# relay_edit.net
KiCad netlist of a schematic drawn in EAGLE
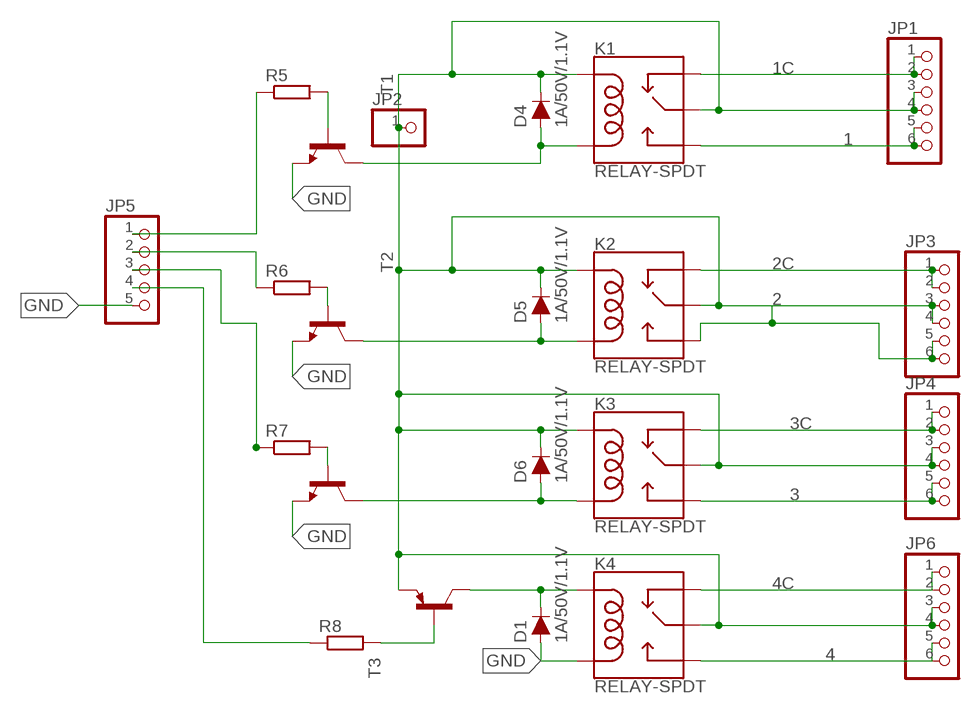
[diagram p0: schematic, sheet 1]

(export (version "E")
  (design (tool "Eeschema 10.0.6"))
  (components
    (comp (ref "D1")
      (value "1A/50V/1.1V")
      (footprint "eagle-import:DIODE-1N4001")
      (libsource (lib "eagle-import") (part "DIODE-PTH"))
    )
    (comp (ref "D4")
      (value "1A/50V/1.1V")
      (footprint "eagle-import:DIODE-1N4001")
      (libsource (lib "eagle-import") (part "DIODE-PTH"))
    )
    (comp (ref "D5")
      (value "1A/50V/1.1V")
      (footprint "eagle-import:DIODE-1N4001")
      (libsource (lib "eagle-import") (part "DIODE-PTH"))
    )
    (comp (ref "D6")
      (value "1A/50V/1.1V")
      (footprint "eagle-import:DIODE-1N4001")
      (libsource (lib "eagle-import") (part "DIODE-PTH"))
    )
    (comp (ref "JP1")
      (value "PINHD-1X6")
      (footprint "eagle-import:1X06")
      (libsource (lib "eagle-import") (part "PINHD-1X6"))
    )
    (comp (ref "JP2")
      (value "PINHD-1X1")
      (footprint "eagle-import:1X01")
      (libsource (lib "eagle-import") (part "PINHD-1X1"))
    )
    (comp (ref "JP3")
      (value "PINHD-1X6")
      (footprint "eagle-import:1X06")
      (libsource (lib "eagle-import") (part "PINHD-1X6"))
    )
    (comp (ref "JP4")
      (value "PINHD-1X6")
      (footprint "eagle-import:1X06")
      (libsource (lib "eagle-import") (part "PINHD-1X6"))
    )
    (comp (ref "JP5")
      (value "PINHD-1X5")
      (footprint "eagle-import:1X05")
      (libsource (lib "eagle-import") (part "PINHD-1X5"))
    )
    (comp (ref "JP6")
      (value "PINHD-1X6")
      (footprint "eagle-import:1X06")
      (libsource (lib "eagle-import") (part "PINHD-1X6"))
    )
    (comp (ref "K1")
      (value "RELAY-SPDT")
      (footprint "eagle-import:RELAY_G5LE")
      (libsource (lib "eagle-import") (part "RELAY-SPDT"))
    )
    (comp (ref "K2")
      (value "RELAY-SPDT")
      (footprint "eagle-import:RELAY_G5LE")
      (libsource (lib "eagle-import") (part "RELAY-SPDT"))
    )
    (comp (ref "K3")
      (value "RELAY-SPDT")
      (footprint "eagle-import:RELAY_G5LE")
      (libsource (lib "eagle-import") (part "RELAY-SPDT"))
    )
    (comp (ref "K4")
      (value "RELAY-SPDT")
      (footprint "eagle-import:RELAY_G5LE")
      (libsource (lib "eagle-import") (part "RELAY-SPDT"))
    )
    (comp (ref "R5")
      (value "R-EU_0204/5")
      (footprint "eagle-import:0204_5")
      (libsource (lib "eagle-import") (part "R-EU_0204/5"))
    )
    (comp (ref "R6")
      (value "R-EU_0204/5")
      (footprint "eagle-import:0204_5")
      (libsource (lib "eagle-import") (part "R-EU_0204/5"))
    )
    (comp (ref "R7")
      (value "R-EU_0204/5")
      (footprint "eagle-import:0204_5")
      (libsource (lib "eagle-import") (part "R-EU_0204/5"))
    )
    (comp (ref "R8")
      (value "R-EU_0204/5")
      (footprint "eagle-import:0204_5")
      (libsource (lib "eagle-import") (part "R-EU_0204/5"))
    )
    (comp (ref "T1")
      (value "2N5401-NPN-TO92-CBE")
      (footprint "eagle-import:TO92-CBE")
      (libsource (lib "eagle-import") (part "-NPN-TO92-CBE2N5401"))
    )
    (comp (ref "T2")
      (value "2N5401-NPN-TO92-CBE")
      (footprint "eagle-import:TO92-CBE")
      (fields (field (name "SPICEPREFIX") "J"))
      (libsource (lib "eagle-import") (part "-NPN-TO92-CBE2N5401"))
    )
    (comp (ref "T3")
      (value "2N4126-PNP-TO92-CBE")
      (footprint "eagle-import:TO92-CBE")
      (libsource (lib "eagle-import") (part "-PNP-TO92-CBE2N4126"))
    )
    (comp (ref "T4")
      (value "2N5401-NPN-TO92-CBE")
      (footprint "eagle-import:TO92-CBE")
      (fields (field (name "SPICEPREFIX") "J"))
      (libsource (lib "eagle-import") (part "-NPN-TO92-CBE2N5401"))
    )
  )
  (nets
    (net (code "1") (name "/1") (class "Default")
      (node (ref "JP1") (pin "5") (pinfunction "5_5") (pintype "passive"))
      (node (ref "JP1") (pin "6") (pinfunction "6_6") (pintype "passive"))
      (node (ref "K1") (pin "3") (pinfunction "NO_3") (pintype "bidirectional"))
    )
    (net (code "2") (name "/1C") (class "Default")
      (node (ref "JP1") (pin "1") (pinfunction "1_1") (pintype "passive"))
      (node (ref "JP1") (pin "2") (pinfunction "2_2") (pintype "passive"))
      (node (ref "K1") (pin "4") (pinfunction "NC_4") (pintype "bidirectional"))
    )
    (net (code "3") (name "/2") (class "Default")
      (node (ref "JP3") (pin "5") (pinfunction "5_5") (pintype "passive"))
      (node (ref "JP3") (pin "6") (pinfunction "6_6") (pintype "passive"))
      (node (ref "K2") (pin "3") (pinfunction "NO_3") (pintype "bidirectional"))
    )
    (net (code "4") (name "/2C") (class "Default")
      (node (ref "JP3") (pin "1") (pinfunction "1_1") (pintype "passive"))
      (node (ref "JP3") (pin "2") (pinfunction "2_2") (pintype "passive"))
      (node (ref "K2") (pin "4") (pinfunction "NC_4") (pintype "bidirectional"))
    )
    (net (code "5") (name "/3") (class "Default")
      (node (ref "JP4") (pin "5") (pinfunction "5_5") (pintype "passive"))
      (node (ref "JP4") (pin "6") (pinfunction "6_6") (pintype "passive"))
      (node (ref "K3") (pin "3") (pinfunction "NO_3") (pintype "bidirectional"))
    )
    (net (code "6") (name "/3C") (class "Default")
      (node (ref "JP4") (pin "1") (pinfunction "1_1") (pintype "passive"))
      (node (ref "JP4") (pin "2") (pinfunction "2_2") (pintype "passive"))
      (node (ref "K3") (pin "4") (pinfunction "NC_4") (pintype "bidirectional"))
    )
    (net (code "7") (name "/4") (class "Default")
      (node (ref "JP6") (pin "5") (pinfunction "5_5") (pintype "passive"))
      (node (ref "JP6") (pin "6") (pinfunction "6_6") (pintype "passive"))
      (node (ref "K4") (pin "3") (pinfunction "NO_3") (pintype "bidirectional"))
    )
    (net (code "8") (name "/4C") (class "Default")
      (node (ref "JP6") (pin "1") (pinfunction "1_1") (pintype "passive"))
      (node (ref "JP6") (pin "2") (pinfunction "2_2") (pintype "passive"))
      (node (ref "K4") (pin "4") (pinfunction "NC_4") (pintype "bidirectional"))
    )
    (net (code "9") (name "GND") (class "Default")
      (node (ref "D1") (pin "A") (pinfunction "A_A") (pintype "passive"))
      (node (ref "JP5") (pin "5") (pinfunction "5_5") (pintype "passive"))
      (node (ref "K4") (pin "5") (pinfunction "COIL2_5") (pintype "bidirectional"))
      (node (ref "T1") (pin "E") (pinfunction "E_E") (pintype "passive"))
      (node (ref "T2") (pin "E") (pinfunction "E_E") (pintype "passive"))
      (node (ref "T4") (pin "E") (pinfunction "E_E") (pintype "passive"))
    )
    (net (code "10") (name "Net-(JP5-Pad1)") (class "Default")
      (node (ref "JP5") (pin "1") (pinfunction "1_1") (pintype "passive"))
      (node (ref "R5") (pin "1") (pinfunction "1_1") (pintype "passive"))
    )
    (net (code "11") (name "Net-(JP5-Pad2)") (class "Default")
      (node (ref "JP5") (pin "2") (pinfunction "2_2") (pintype "passive"))
      (node (ref "R6") (pin "1") (pinfunction "1_1") (pintype "passive"))
    )
    (net (code "12") (name "Net-(JP5-Pad3)") (class "Default")
      (node (ref "JP5") (pin "3") (pinfunction "3_3") (pintype "passive"))
      (node (ref "R7") (pin "1") (pinfunction "1_1") (pintype "passive"))
    )
    (net (code "13") (name "Net-(JP5-Pad4)") (class "Default")
      (node (ref "JP5") (pin "4") (pinfunction "4_4") (pintype "passive"))
      (node (ref "R8") (pin "1") (pinfunction "1_1") (pintype "passive"))
    )
    (net (code "14") (name "Net-(K1-COIL1)") (class "Default")
      (node (ref "D4") (pin "C") (pinfunction "C_C") (pintype "passive"))
      (node (ref "D5") (pin "C") (pinfunction "C_C") (pintype "passive"))
      (node (ref "D6") (pin "C") (pinfunction "C_C") (pintype "passive"))
      (node (ref "JP1") (pin "3") (pinfunction "3_3") (pintype "passive"))
      (node (ref "JP1") (pin "4") (pinfunction "4_4") (pintype "passive"))
      (node (ref "JP2") (pin "1") (pinfunction "1_1") (pintype "passive"))
      (node (ref "JP3") (pin "3") (pinfunction "3_3") (pintype "passive"))
      (node (ref "JP3") (pin "4") (pinfunction "4_4") (pintype "passive"))
      (node (ref "JP4") (pin "3") (pinfunction "3_3") (pintype "passive"))
      (node (ref "JP4") (pin "4") (pinfunction "4_4") (pintype "passive"))
      (node (ref "JP6") (pin "3") (pinfunction "3_3") (pintype "passive"))
      (node (ref "JP6") (pin "4") (pinfunction "4_4") (pintype "passive"))
      (node (ref "K1") (pin "1") (pinfunction "MAIN_1") (pintype "bidirectional"))
      (node (ref "K1") (pin "2") (pinfunction "COIL1_2") (pintype "bidirectional"))
      (node (ref "K2") (pin "1") (pinfunction "MAIN_1") (pintype "bidirectional"))
      (node (ref "K2") (pin "2") (pinfunction "COIL1_2") (pintype "bidirectional"))
      (node (ref "K3") (pin "1") (pinfunction "MAIN_1") (pintype "bidirectional"))
      (node (ref "K3") (pin "2") (pinfunction "COIL1_2") (pintype "bidirectional"))
      (node (ref "K4") (pin "1") (pinfunction "MAIN_1") (pintype "bidirectional"))
      (node (ref "T3") (pin "E") (pinfunction "E_E") (pintype "passive"))
    )
    (net (code "15") (name "Net-(K1-COIL2)") (class "Default")
      (node (ref "D4") (pin "A") (pinfunction "A_A") (pintype "passive"))
      (node (ref "K1") (pin "5") (pinfunction "COIL2_5") (pintype "bidirectional"))
      (node (ref "T1") (pin "C") (pinfunction "C_C") (pintype "passive"))
    )
    (net (code "16") (name "Net-(K2-COIL2)") (class "Default")
      (node (ref "D5") (pin "A") (pinfunction "A_A") (pintype "passive"))
      (node (ref "K2") (pin "5") (pinfunction "COIL2_5") (pintype "bidirectional"))
      (node (ref "T2") (pin "C") (pinfunction "C_C") (pintype "passive"))
    )
    (net (code "17") (name "Net-(K3-COIL2)") (class "Default")
      (node (ref "D6") (pin "A") (pinfunction "A_A") (pintype "passive"))
      (node (ref "K3") (pin "5") (pinfunction "COIL2_5") (pintype "bidirectional"))
      (node (ref "T4") (pin "C") (pinfunction "C_C") (pintype "passive"))
    )
    (net (code "18") (name "Net-(K4-COIL1)") (class "Default")
      (node (ref "D1") (pin "C") (pinfunction "C_C") (pintype "passive"))
      (node (ref "K4") (pin "2") (pinfunction "COIL1_2") (pintype "bidirectional"))
      (node (ref "T3") (pin "C") (pinfunction "C_C") (pintype "passive"))
    )
    (net (code "19") (name "Net-(R5-Pad2)") (class "Default")
      (node (ref "R5") (pin "2") (pinfunction "2_2") (pintype "passive"))
      (node (ref "T1") (pin "B") (pinfunction "B_B") (pintype "passive"))
    )
    (net (code "20") (name "Net-(R6-Pad2)") (class "Default")
      (node (ref "R6") (pin "2") (pinfunction "2_2") (pintype "passive"))
      (node (ref "T2") (pin "B") (pinfunction "B_B") (pintype "passive"))
    )
    (net (code "21") (name "Net-(R7-Pad2)") (class "Default")
      (node (ref "R7") (pin "2") (pinfunction "2_2") (pintype "passive"))
      (node (ref "T4") (pin "B") (pinfunction "B_B") (pintype "passive"))
    )
    (net (code "22") (name "Net-(R8-Pad2)") (class "Default")
      (node (ref "R8") (pin "2") (pinfunction "2_2") (pintype "passive"))
      (node (ref "T3") (pin "B") (pinfunction "B_B") (pintype "passive"))
    )
  )
)
